# design.net
KiCad netlist of a schematic drawn in Altium Designer
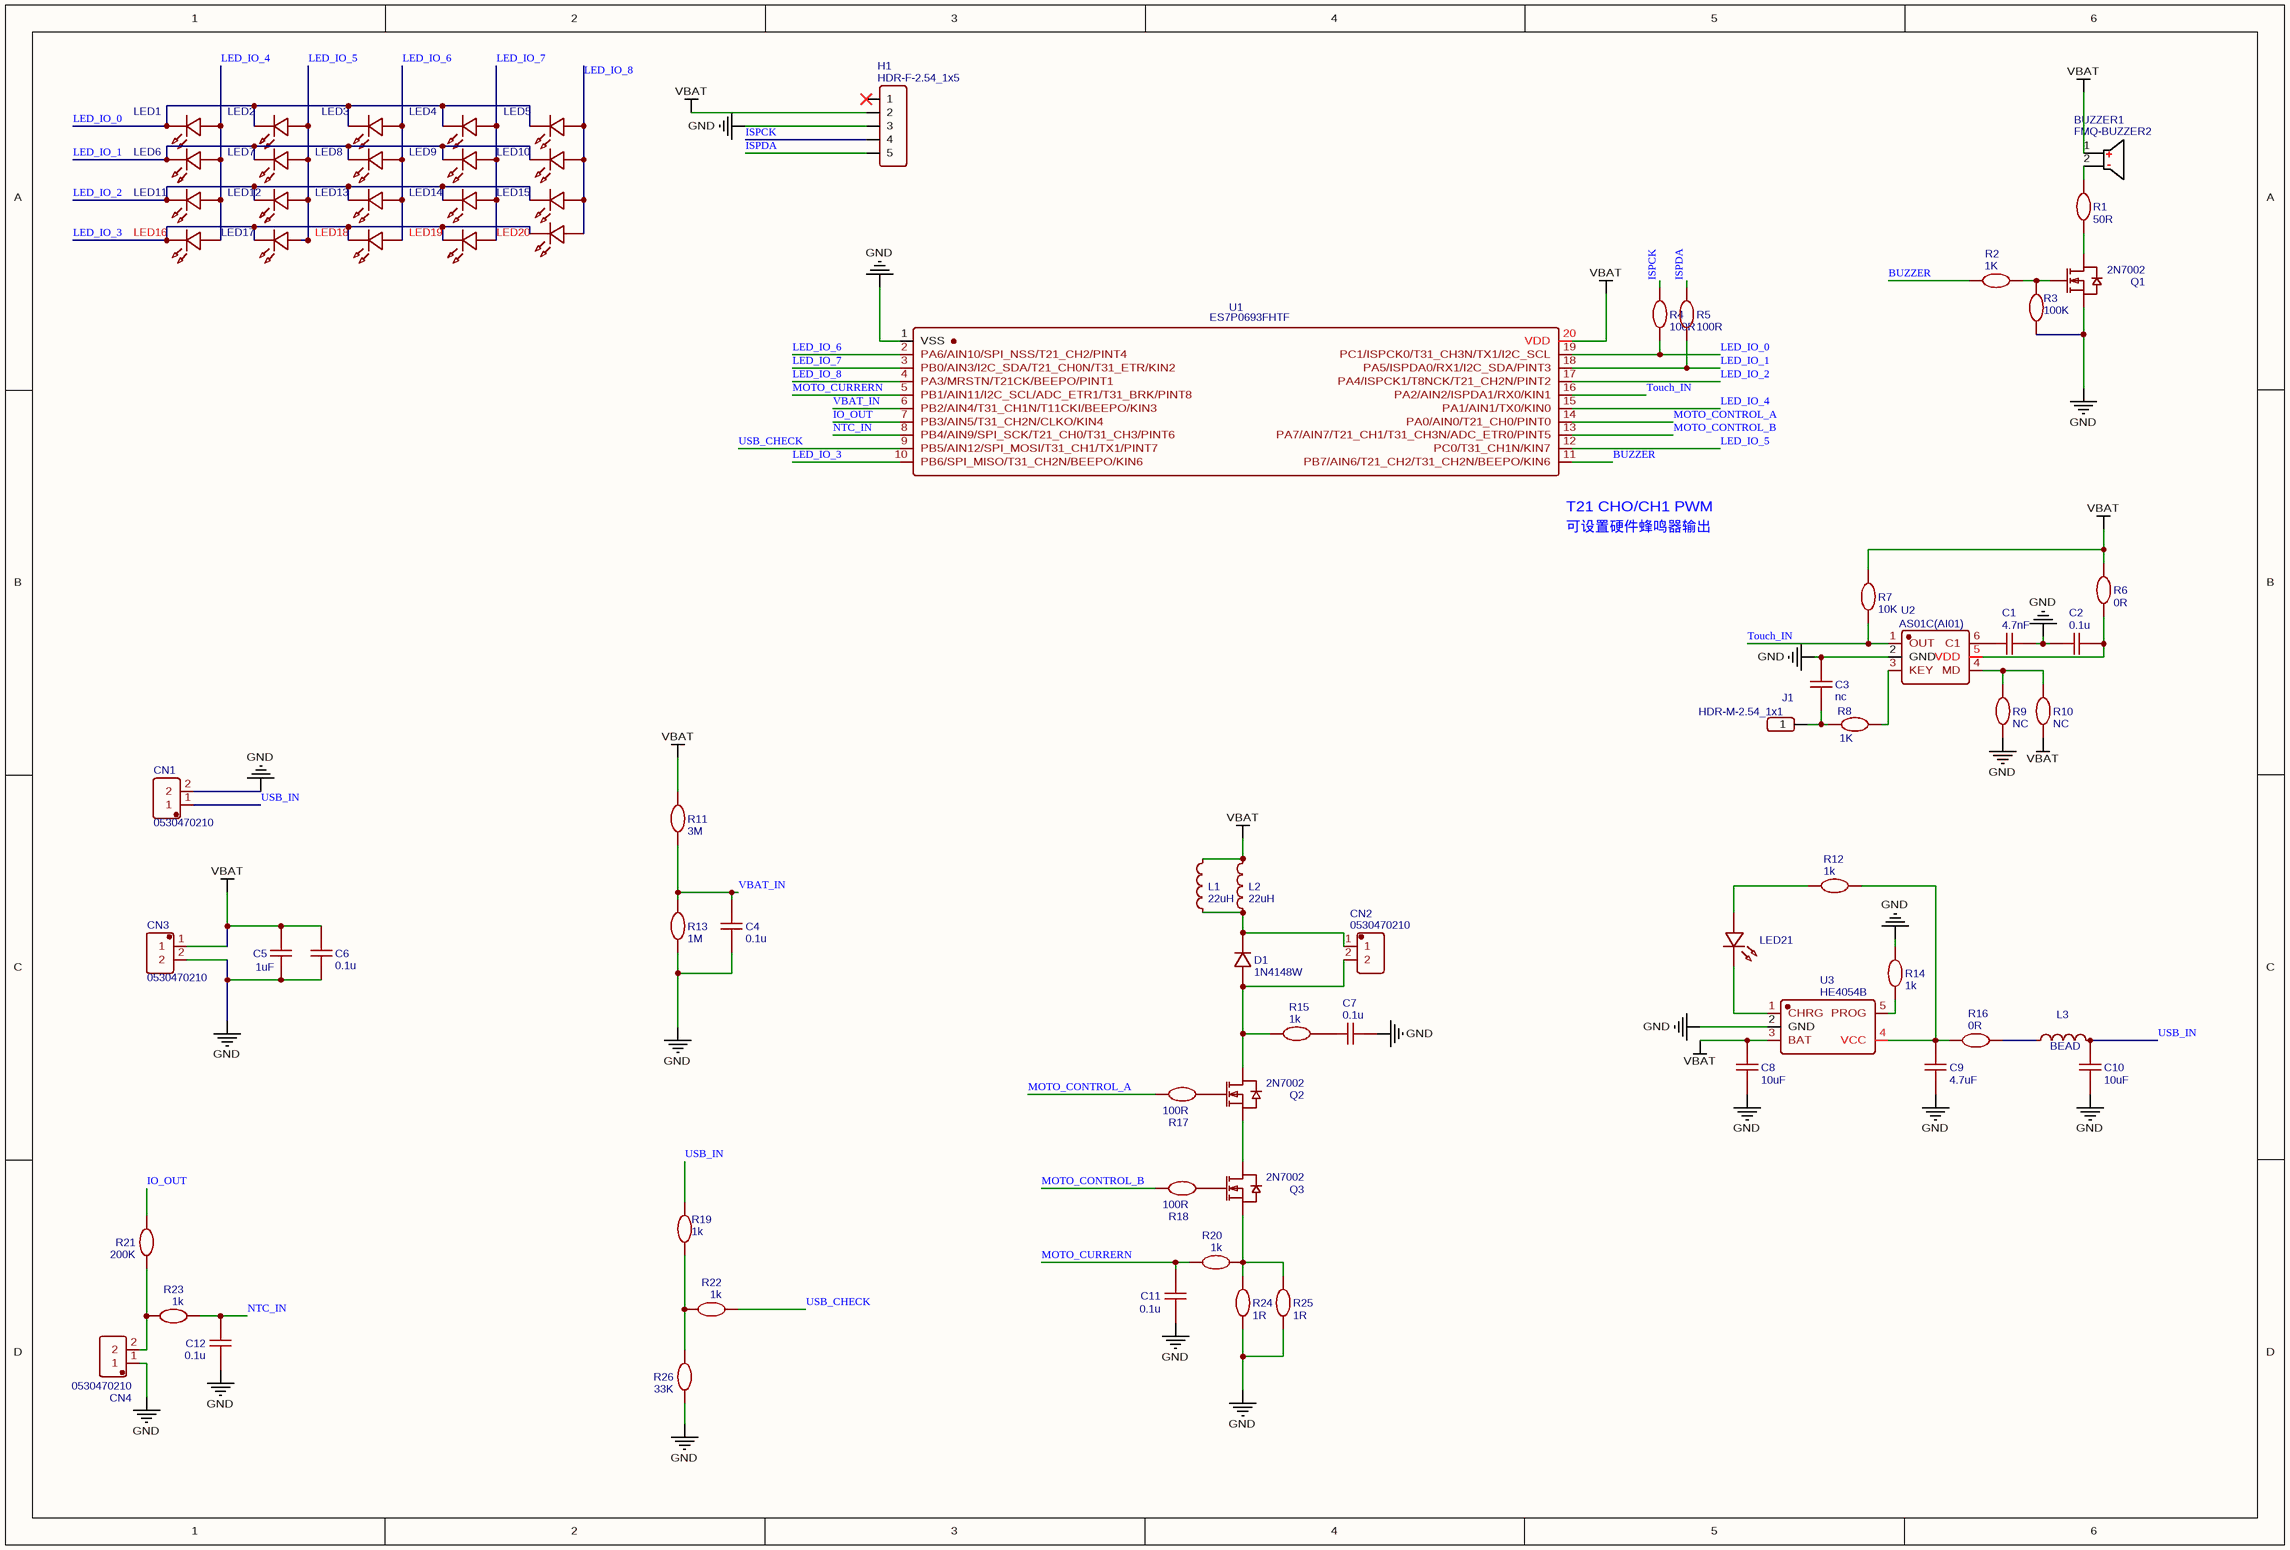
[diagram p0: 搅拌杯原理图.schdoc]

(export (version "E")
  (design (tool "Eeschema 10.0.6"))
  (components
    (comp (ref "BUZZER1")
      (value "FMQ-BUZZER2")
      (footprint "BUZ-TH_BD12.0-P7.60-D0.6-FD")
      (fields (field (name "BOM_SUPPLIER PART") "C9900006103") (field (name "CONTRIBUTOR") "LCSC"))
      (libsource (lib "altium-import") (part "root_0_FMQ-BUZZER2_"))
    )
    (comp (ref "C1")
      (value "4.7nF")
      (footprint "C0603")
      (fields (field (name "CONTRIBUTOR") "LCEDA_Lib"))
      (libsource (lib "altium-import") (part "root_0_4.7nF_"))
    )
    (comp (ref "C2")
      (value "0.1u")
      (footprint "C0603")
      (fields (field (name "CONTRIBUTOR") "LCEDA_Lib"))
      (libsource (lib "altium-import") (part "root_0_0.1u_"))
    )
    (comp (ref "C3")
      (value "nc")
      (footprint "C0603")
      (fields (field (name "CONTRIBUTOR") "LCEDA_Lib"))
      (libsource (lib "altium-import") (part "root_1_nc_"))
    )
    (comp (ref "C4")
      (value "0.1u")
      (footprint "C0603")
      (fields (field (name "CONTRIBUTOR") "LCEDA_Lib"))
      (libsource (lib "") (part "root_1_0.1u__1"))
    )
    (comp (ref "C5")
      (value "1uF")
      (footprint "C0603")
      (fields (field (name "CONTRIBUTOR") "LCEDA_Lib"))
      (libsource (lib "altium-import") (part "root_3_1uF_"))
    )
    (comp (ref "C6")
      (value "0.1u")
      (footprint "C0603")
      (fields (field (name "CONTRIBUTOR") "LCEDA_Lib"))
      (libsource (lib "altium-import") (part "root_3_0.1u_"))
    )
    (comp (ref "C7")
      (value "0.1u")
      (footprint "C0603")
      (fields (field (name "CONTRIBUTOR") "LCEDA_Lib"))
      (libsource (lib "altium-import") (part "root_2_0.1u_"))
    )
    (comp (ref "C8")
      (value "10uF")
      (footprint "C0603")
      (fields (field (name "CONTRIBUTOR") "LCEDA_Lib"))
      (libsource (lib "altium-import") (part "root_1_10uF_"))
    )
    (comp (ref "C9")
      (value "4.7uF")
      (footprint "C0603")
      (fields (field (name "CONTRIBUTOR") "LCEDA_Lib"))
      (libsource (lib "altium-import") (part "root_1_4.7uF_"))
    )
    (comp (ref "C10")
      (value "10uF")
      (footprint "C0603")
      (fields (field (name "CONTRIBUTOR") "LCEDA_Lib"))
      (libsource (lib "altium-import") (part "root_1_10uF_"))
    )
    (comp (ref "C11")
      (value "0.1u")
      (footprint "C0603")
      (fields (field (name "CONTRIBUTOR") "LCEDA_Lib"))
      (libsource (lib "altium-import") (part "root_1_0.1u_"))
    )
    (comp (ref "C12")
      (value "0.1u")
      (footprint "C0603")
      (fields (field (name "CONTRIBUTOR") "LCEDA_Lib"))
      (libsource (lib "") (part "root_3_0.1u__1"))
    )
    (comp (ref "CN1")
      (value "0530470210")
      (footprint "CONN-TH_0530470210")
      (fields (field (name "BOM_SUPPLIER PART") "C114130") (field (name "CONTRIBUTOR") "LCSC"))
      (libsource (lib "altium-import") (part "root_0_mirrored_0530470210_"))
    )
    (comp (ref "CN2")
      (value "0530470210")
      (footprint "CONN-TH_0530470210")
      (fields (field (name "BOM_SUPPLIER PART") "C114130") (field (name "CONTRIBUTOR") "LCSC"))
      (libsource (lib "altium-import") (part "root_0_0530470210_"))
    )
    (comp (ref "CN3")
      (value "0530470210")
      (footprint "CONN-TH_0530470210")
      (fields (field (name "BOM_SUPPLIER PART") "C114130") (field (name "CONTRIBUTOR") "LCSC"))
      (libsource (lib "") (part "root_0_mirrored_0530470210__1"))
    )
    (comp (ref "CN4")
      (value "0530470210")
      (footprint "CONN-TH_0530470210")
      (fields (field (name "BOM_SUPPLIER PART") "C114130") (field (name "CONTRIBUTOR") "LCSC"))
      (libsource (lib "") (part "root_0_0530470210__1"))
    )
    (comp (ref "D1")
      (value "1N4148W")
      (footprint "SOD-123FL_L2.6-W1.6-LS3.4-RD")
      (fields (field (name "BOM_SUPPLIER PART") "C129216") (field (name "CONTRIBUTOR") "LCEDA_Lib"))
      (libsource (lib "altium-import") (part "root_1_1N4148W_"))
    )
    (comp (ref "H1")
      (value "HDR-F-2.54_1x5")
      (footprint "1.27mm_5PIN")
      (fields (field (name "BOM_SUPPLIER PART") "C50950") (field (name "CONTRIBUTOR") "LCEDA_Lib"))
      (libsource (lib "altium-import") (part "root_0_HDR-F-2.54_1x5_"))
    )
    (comp (ref "J1")
      (value "HDR-M-2.54_1x1")
      (footprint "HDR-M-2.54_1X1")
      (fields (field (name "BOM_SUPPLIER PART") "C81276") (field (name "CONTRIBUTOR") "LCEDA_Lib"))
      (libsource (lib "altium-import") (part "root_2_HDR-M-2.54_1x1_"))
    )
    (comp (ref "L1")
      (value "22uH")
      (footprint "L0603")
      (fields (field (name "CONTRIBUTOR") "LCEDA_Lib"))
      (libsource (lib "altium-import") (part "root_1_22uH_"))
    )
    (comp (ref "L2")
      (value "22uH")
      (footprint "L0603")
      (fields (field (name "CONTRIBUTOR") "LCEDA_Lib"))
      (libsource (lib "altium-import") (part "root_1_22uH_"))
    )
    (comp (ref "L3")
      (value "BEAD")
      (footprint "L0603")
      (fields (field (name "CONTRIBUTOR") "LCEDA_Lib"))
      (libsource (lib "altium-import") (part "root_0_22uH_"))
    )
    (comp (ref "LED1")
      (value "LED-0603_W")
      (footprint "LED0603-FD_WHITE")
      (fields
        (field (name "BOM_MANUFACTURER PART") "17-21SURC/S530-A3/TR8")
        (field (name "BOM_SUPPLIER PART") "C72037")
        (field (name "CONTRIBUTOR") "LCEDA_Lib")
      )
      (libsource (lib "altium-import") (part "root_2_LED-0603_W_"))
    )
    (comp (ref "LED2")
      (value "LED-0603_W")
      (footprint "LED0603-FD_WHITE")
      (fields
        (field (name "BOM_MANUFACTURER PART") "17-21SURC/S530-A3/TR8")
        (field (name "BOM_SUPPLIER PART") "C72037")
        (field (name "CONTRIBUTOR") "LCEDA_Lib")
      )
      (libsource (lib "altium-import") (part "root_2_LED-0603_W_"))
    )
    (comp (ref "LED3")
      (value "LED-0603_W")
      (footprint "LED0603-FD_WHITE")
      (fields
        (field (name "BOM_MANUFACTURER PART") "17-21SURC/S530-A3/TR8")
        (field (name "BOM_SUPPLIER PART") "C72037")
        (field (name "CONTRIBUTOR") "LCEDA_Lib")
      )
      (libsource (lib "altium-import") (part "root_2_LED-0603_W_"))
    )
    (comp (ref "LED4")
      (value "LED-0603_W")
      (footprint "LED0603-FD_WHITE")
      (fields
        (field (name "BOM_MANUFACTURER PART") "17-21SURC/S530-A3/TR8")
        (field (name "BOM_SUPPLIER PART") "C72037")
        (field (name "CONTRIBUTOR") "LCEDA_Lib")
      )
      (libsource (lib "altium-import") (part "root_2_LED-0603_W_"))
    )
    (comp (ref "LED5")
      (value "LED-0603_W")
      (footprint "LED0603-FD_WHITE")
      (fields
        (field (name "BOM_MANUFACTURER PART") "17-21SURC/S530-A3/TR8")
        (field (name "BOM_SUPPLIER PART") "C72037")
        (field (name "CONTRIBUTOR") "LCEDA_Lib")
      )
      (libsource (lib "altium-import") (part "root_2_LED-0603_W_"))
    )
    (comp (ref "LED6")
      (value "LED-0603_W")
      (footprint "LED0603-FD_WHITE")
      (fields
        (field (name "BOM_MANUFACTURER PART") "17-21SURC/S530-A3/TR8")
        (field (name "BOM_SUPPLIER PART") "C72037")
        (field (name "CONTRIBUTOR") "LCEDA_Lib")
      )
      (libsource (lib "altium-import") (part "root_2_LED-0603_W_"))
    )
    (comp (ref "LED7")
      (value "LED-0603_W")
      (footprint "LED0603-FD_WHITE")
      (fields
        (field (name "BOM_MANUFACTURER PART") "17-21SURC/S530-A3/TR8")
        (field (name "BOM_SUPPLIER PART") "C72037")
        (field (name "CONTRIBUTOR") "LCEDA_Lib")
      )
      (libsource (lib "altium-import") (part "root_2_LED-0603_W_"))
    )
    (comp (ref "LED8")
      (value "LED-0603_W")
      (footprint "LED0603-FD_WHITE")
      (fields
        (field (name "BOM_MANUFACTURER PART") "17-21SURC/S530-A3/TR8")
        (field (name "BOM_SUPPLIER PART") "C72037")
        (field (name "CONTRIBUTOR") "LCEDA_Lib")
      )
      (libsource (lib "altium-import") (part "root_2_LED-0603_W_"))
    )
    (comp (ref "LED9")
      (value "LED-0603_W")
      (footprint "LED0603-FD_WHITE")
      (fields
        (field (name "BOM_MANUFACTURER PART") "17-21SURC/S530-A3/TR8")
        (field (name "BOM_SUPPLIER PART") "C72037")
        (field (name "CONTRIBUTOR") "LCEDA_Lib")
      )
      (libsource (lib "altium-import") (part "root_2_LED-0603_W_"))
    )
    (comp (ref "LED10")
      (value "LED-0603_W")
      (footprint "LED0603-FD_WHITE")
      (fields
        (field (name "BOM_MANUFACTURER PART") "17-21SURC/S530-A3/TR8")
        (field (name "BOM_SUPPLIER PART") "C72037")
        (field (name "CONTRIBUTOR") "LCEDA_Lib")
      )
      (libsource (lib "altium-import") (part "root_2_LED-0603_W_"))
    )
    (comp (ref "LED11")
      (value "LED-0603_W")
      (footprint "LED0603-FD_WHITE")
      (fields
        (field (name "BOM_MANUFACTURER PART") "17-21SURC/S530-A3/TR8")
        (field (name "BOM_SUPPLIER PART") "C72037")
        (field (name "CONTRIBUTOR") "LCEDA_Lib")
      )
      (libsource (lib "altium-import") (part "root_2_LED-0603_W_"))
    )
    (comp (ref "LED12")
      (value "LED-0603_W")
      (footprint "LED0603-FD_WHITE")
      (fields
        (field (name "BOM_MANUFACTURER PART") "17-21SURC/S530-A3/TR8")
        (field (name "BOM_SUPPLIER PART") "C72037")
        (field (name "CONTRIBUTOR") "LCEDA_Lib")
      )
      (libsource (lib "altium-import") (part "root_2_LED-0603_W_"))
    )
    (comp (ref "LED13")
      (value "LED-0603_W")
      (footprint "LED0603-FD_WHITE")
      (fields
        (field (name "BOM_MANUFACTURER PART") "17-21SURC/S530-A3/TR8")
        (field (name "BOM_SUPPLIER PART") "C72037")
        (field (name "CONTRIBUTOR") "LCEDA_Lib")
      )
      (libsource (lib "altium-import") (part "root_2_LED-0603_W_"))
    )
    (comp (ref "LED14")
      (value "LED-0603_W")
      (footprint "LED0603-FD_WHITE")
      (fields
        (field (name "BOM_MANUFACTURER PART") "17-21SURC/S530-A3/TR8")
        (field (name "BOM_SUPPLIER PART") "C72037")
        (field (name "CONTRIBUTOR") "LCEDA_Lib")
      )
      (libsource (lib "altium-import") (part "root_2_LED-0603_W_"))
    )
    (comp (ref "LED15")
      (value "LED-0603_W")
      (footprint "LED0603-FD_WHITE")
      (fields
        (field (name "BOM_MANUFACTURER PART") "17-21SURC/S530-A3/TR8")
        (field (name "BOM_SUPPLIER PART") "C72037")
        (field (name "CONTRIBUTOR") "LCEDA_Lib")
      )
      (libsource (lib "altium-import") (part "root_2_LED-0603_W_"))
    )
    (comp (ref "LED16")
      (value "LED-0603_W")
      (footprint "LED0603-FD_WHITE")
      (fields
        (field (name "BOM_MANUFACTURER PART") "17-21SURC/S530-A3/TR8")
        (field (name "BOM_SUPPLIER PART") "C72037")
        (field (name "CONTRIBUTOR") "LCEDA_Lib")
      )
      (libsource (lib "altium-import") (part "root_2_LED-0603_W_"))
    )
    (comp (ref "LED17")
      (value "LED-0603_W")
      (footprint "LED0603-FD_WHITE")
      (fields
        (field (name "BOM_MANUFACTURER PART") "17-21SURC/S530-A3/TR8")
        (field (name "BOM_SUPPLIER PART") "C72037")
        (field (name "CONTRIBUTOR") "LCEDA_Lib")
      )
      (libsource (lib "altium-import") (part "root_2_LED-0603_W_"))
    )
    (comp (ref "LED18")
      (value "LED-0603_W")
      (footprint "LED0603-FD_WHITE")
      (fields
        (field (name "BOM_MANUFACTURER PART") "17-21SURC/S530-A3/TR8")
        (field (name "BOM_SUPPLIER PART") "C72037")
        (field (name "CONTRIBUTOR") "LCEDA_Lib")
      )
      (libsource (lib "altium-import") (part "root_2_LED-0603_W_"))
    )
    (comp (ref "LED19")
      (value "LED-0603_W")
      (footprint "LED0603-FD_WHITE")
      (fields
        (field (name "BOM_MANUFACTURER PART") "17-21SURC/S530-A3/TR8")
        (field (name "BOM_SUPPLIER PART") "C72037")
        (field (name "CONTRIBUTOR") "LCEDA_Lib")
      )
      (libsource (lib "altium-import") (part "root_2_LED-0603_W_"))
    )
    (comp (ref "LED20")
      (value "LED-0603_W")
      (footprint "LED0603-FD_WHITE")
      (fields
        (field (name "BOM_MANUFACTURER PART") "17-21SURC/S530-A3/TR8")
        (field (name "BOM_SUPPLIER PART") "C72037")
        (field (name "CONTRIBUTOR") "LCEDA_Lib")
      )
      (libsource (lib "altium-import") (part "root_2_LED-0603_W_"))
    )
    (comp (ref "LED21")
      (value "LED-0603_W")
      (footprint "LED0603-FD_WHITE")
      (fields
        (field (name "BOM_MANUFACTURER PART") "17-21SURC/S530-A3/TR8")
        (field (name "BOM_SUPPLIER PART") "C72037")
        (field (name "CONTRIBUTOR") "LCEDA_Lib")
      )
      (libsource (lib "altium-import") (part "root_3_LED-0603_W_"))
    )
    (comp (ref "Q1")
      (value "2N7002")
      (footprint "SOT-23_L2.9-W1.3-P0.95-LS2.4-BR")
      (fields
        (field (name "BOM_MANUFACTURER PART") "2N7002,215")
        (field (name "BOM_SUPPLIER PART") "C65189")
        (field (name "CONTRIBUTOR") "LCEDA_Lib")
      )
      (libsource (lib "altium-import") (part "root_2_2N7002_"))
    )
    (comp (ref "Q2")
      (value "2N7002")
      (footprint "SOT-23_L2.9-W1.3-P0.95-LS2.4-BR")
      (fields
        (field (name "BOM_MANUFACTURER PART") "2N7002,215")
        (field (name "BOM_SUPPLIER PART") "C65189")
        (field (name "CONTRIBUTOR") "LCEDA_Lib")
      )
      (libsource (lib "altium-import") (part "root_2_2N7002_"))
    )
    (comp (ref "Q3")
      (value "2N7002")
      (footprint "SOT-23_L2.9-W1.3-P0.95-LS2.4-BR")
      (fields
        (field (name "BOM_MANUFACTURER PART") "2N7002,215")
        (field (name "BOM_SUPPLIER PART") "C65189")
        (field (name "CONTRIBUTOR") "LCEDA_Lib")
      )
      (libsource (lib "altium-import") (part "root_2_2N7002_"))
    )
    (comp (ref "R1")
      (value "50R")
      (footprint "R0603")
      (fields (field (name "CONTRIBUTOR") "LCEDA_Lib"))
      (libsource (lib "altium-import") (part "root_3_100R_"))
    )
    (comp (ref "R2")
      (value "1K")
      (footprint "R0603")
      (fields (field (name "CONTRIBUTOR") "LCEDA_Lib"))
      (libsource (lib "altium-import") (part "root_2_1K_"))
    )
    (comp (ref "R3")
      (value "100K")
      (footprint "R0603")
      (fields (field (name "CONTRIBUTOR") "LCEDA_Lib"))
      (libsource (lib "altium-import") (part "root_3_1K_"))
    )
    (comp (ref "R4")
      (value "100R")
      (footprint "R0603")
      (fields (field (name "CONTRIBUTOR") "LCEDA_Lib"))
      (libsource (lib "altium-import") (part "root_3_100R_"))
    )
    (comp (ref "R5")
      (value "100R")
      (footprint "R0603")
      (fields (field (name "CONTRIBUTOR") "LCEDA_Lib"))
      (libsource (lib "altium-import") (part "root_3_100R_"))
    )
    (comp (ref "R6")
      (value "0R")
      (footprint "R0603")
      (fields (field (name "CONTRIBUTOR") "LCEDA_Lib"))
      (libsource (lib "altium-import") (part "root_1_NC_"))
    )
    (comp (ref "R7")
      (value "10K")
      (footprint "R0603")
      (fields (field (name "CONTRIBUTOR") "LCEDA_Lib"))
      (libsource (lib "altium-import") (part "root_1_NC_"))
    )
    (comp (ref "R8")
      (value "1K")
      (footprint "R0603")
      (fields (field (name "CONTRIBUTOR") "LCEDA_Lib"))
      (libsource (lib "altium-import") (part "root_2_1K_"))
    )
    (comp (ref "R9")
      (value "NC")
      (footprint "R0603")
      (fields (field (name "CONTRIBUTOR") "LCEDA_Lib"))
      (libsource (lib "altium-import") (part "root_1_NC_"))
    )
    (comp (ref "R10")
      (value "NC")
      (footprint "R0603")
      (fields (field (name "CONTRIBUTOR") "LCEDA_Lib"))
      (libsource (lib "altium-import") (part "root_1_NC_"))
    )
    (comp (ref "R11")
      (value "3M")
      (footprint "R0603")
      (fields (field (name "CONTRIBUTOR") "LCEDA_Lib"))
      (libsource (lib "altium-import") (part "root_1_430k_"))
    )
    (comp (ref "R12")
      (value "1k")
      (footprint "R0603")
      (fields (field (name "CONTRIBUTOR") "LCEDA_Lib"))
      (libsource (lib "") (part "root_2_1k__1"))
    )
    (comp (ref "R13")
      (value "1M")
      (footprint "R0603")
      (fields (field (name "CONTRIBUTOR") "LCEDA_Lib"))
      (libsource (lib "altium-import") (part "root_1_430K_"))
    )
    (comp (ref "R14")
      (value "1k")
      (footprint "R0603")
      (fields (field (name "CONTRIBUTOR") "LCEDA_Lib"))
      (libsource (lib "altium-import") (part "root_1_1k_"))
    )
    (comp (ref "R15")
      (value "1k")
      (footprint "R0603")
      (fields (field (name "CONTRIBUTOR") "LCEDA_Lib"))
      (libsource (lib "") (part "root_2_1k__1"))
    )
    (comp (ref "R16")
      (value "0R")
      (footprint "R0603")
      (fields (field (name "CONTRIBUTOR") "LCEDA_Lib"))
      (libsource (lib "altium-import") (part "root_0_NC_"))
    )
    (comp (ref "R17")
      (value "100R")
      (footprint "R0603")
      (fields (field (name "CONTRIBUTOR") "LCEDA_Lib"))
      (libsource (lib "altium-import") (part "root_2_100R_"))
    )
    (comp (ref "R18")
      (value "100R")
      (footprint "R0603")
      (fields (field (name "CONTRIBUTOR") "LCEDA_Lib"))
      (libsource (lib "altium-import") (part "root_2_100R_"))
    )
    (comp (ref "R19")
      (value "1k")
      (footprint "R0603")
      (fields (field (name "CONTRIBUTOR") "LCEDA_Lib"))
      (libsource (lib "altium-import") (part "root_3_1k_"))
    )
    (comp (ref "R20")
      (value "1k")
      (footprint "R0603")
      (fields (field (name "CONTRIBUTOR") "LCEDA_Lib"))
      (libsource (lib "altium-import") (part "root_0_1k_"))
    )
    (comp (ref "R21")
      (value "200K")
      (footprint "R0603")
      (fields (field (name "CONTRIBUTOR") "LCEDA_Lib"))
      (libsource (lib "altium-import") (part "root_3_33K_"))
    )
    (comp (ref "R22")
      (value "1k")
      (footprint "R0603")
      (fields (field (name "CONTRIBUTOR") "LCEDA_Lib"))
      (libsource (lib "altium-import") (part "root_2_1k_"))
    )
    (comp (ref "R23")
      (value "1k")
      (footprint "R0603")
      (fields (field (name "CONTRIBUTOR") "LCEDA_Lib"))
      (libsource (lib "altium-import") (part "root_2_1k_"))
    )
    (comp (ref "R24")
      (value "1R")
      (footprint "R1206")
      (fields (field (name "CONTRIBUTOR") "LCEDA_Lib"))
      (libsource (lib "altium-import") (part "root_1_1R_"))
    )
    (comp (ref "R25")
      (value "1R")
      (footprint "R1206")
      (fields (field (name "CONTRIBUTOR") "LCEDA_Lib"))
      (libsource (lib "altium-import") (part "root_1_1R_"))
    )
    (comp (ref "R26")
      (value "33K")
      (footprint "R0603")
      (fields (field (name "CONTRIBUTOR") "LCEDA_Lib"))
      (libsource (lib "altium-import") (part "root_3_33K_"))
    )
    (comp (ref "U1")
      (value "ES7P0693FHTF")
      (footprint "TSOP20")
      (fields (field (name "CONTRIBUTOR") "zime_zl"))
      (libsource (lib "altium-import") (part "root_0_ES7P0693FHTF_"))
    )
    (comp (ref "U2")
      (value "AS01C(AI01)")
      (footprint "SOT-23-6_L2.9-W1.6-P0.95-LS2.8-BL")
      (fields (field (name "BOM_SUPPLIER PART") "C389617") (field (name "CONTRIBUTOR") "LCSC"))
      (libsource (lib "altium-import") (part "root_0_AS01C(AI01)_"))
    )
    (comp (ref "U3")
      (value "HE4054B")
      (footprint "SOT-23-5_L3.0-W1.7-P0.95-LS2.8-BR")
      (fields (field (name "BOM_SUPPLIER PART") "C711953") (field (name "CONTRIBUTOR") "LCSC"))
      (libsource (lib "altium-import") (part "root_0_HE4054B_"))
    )
  )
  (nets
    (net (code "1") (name "/BUZZER") (class "Default")
      (node (ref "R2") (pin "2") (pinfunction "2_2") (pintype "passive"))
      (node (ref "U1") (pin "11") (pinfunction "PB7/AIN6/T21_CH2/T31_CH2N/BEEPO/KIN6_11") (pintype "passive"))
    )
    (net (code "2") (name "/IO_OUT") (class "Default")
      (node (ref "R21") (pin "1") (pinfunction "1_1") (pintype "passive"))
      (node (ref "U1") (pin "7") (pinfunction "PB3/AIN5/T31_CH2N/CLKO/KIN4_7") (pintype "passive"))
    )
    (net (code "3") (name "/ISPCK") (class "Default")
      (node (ref "H1") (pin "4") (pinfunction "4_4") (pintype "passive"))
      (node (ref "R4") (pin "1") (pinfunction "1_1") (pintype "passive"))
    )
    (net (code "4") (name "/ISPDA") (class "Default")
      (node (ref "H1") (pin "5") (pinfunction "5_5") (pintype "passive"))
      (node (ref "R5") (pin "1") (pinfunction "1_1") (pintype "passive"))
    )
    (net (code "5") (name "/LED_IO_0") (class "Default")
      (node (ref "LED1") (pin "2") (pinfunction "2_2") (pintype "passive"))
      (node (ref "LED2") (pin "2") (pinfunction "2_2") (pintype "passive"))
      (node (ref "LED3") (pin "2") (pinfunction "2_2") (pintype "passive"))
      (node (ref "LED4") (pin "2") (pinfunction "2_2") (pintype "passive"))
      (node (ref "LED5") (pin "2") (pinfunction "2_2") (pintype "passive"))
      (node (ref "R4") (pin "2") (pinfunction "2_2") (pintype "passive"))
      (node (ref "U1") (pin "19") (pinfunction "PC1/ISPCK0/T31_CH3N/TX1/I2C_SCL_19") (pintype "passive"))
    )
    (net (code "6") (name "/LED_IO_1") (class "Default")
      (node (ref "LED10") (pin "2") (pinfunction "2_2") (pintype "passive"))
      (node (ref "LED6") (pin "2") (pinfunction "2_2") (pintype "passive"))
      (node (ref "LED7") (pin "2") (pinfunction "2_2") (pintype "passive"))
      (node (ref "LED8") (pin "2") (pinfunction "2_2") (pintype "passive"))
      (node (ref "LED9") (pin "2") (pinfunction "2_2") (pintype "passive"))
      (node (ref "R5") (pin "2") (pinfunction "2_2") (pintype "passive"))
      (node (ref "U1") (pin "18") (pinfunction "PA5/ISPDA0/RX1/I2C_SDA/PINT3_18") (pintype "passive"))
    )
    (net (code "7") (name "/LED_IO_2") (class "Default")
      (node (ref "LED11") (pin "2") (pinfunction "2_2") (pintype "passive"))
      (node (ref "LED12") (pin "2") (pinfunction "2_2") (pintype "passive"))
      (node (ref "LED13") (pin "2") (pinfunction "2_2") (pintype "passive"))
      (node (ref "LED14") (pin "2") (pinfunction "2_2") (pintype "passive"))
      (node (ref "LED15") (pin "2") (pinfunction "2_2") (pintype "passive"))
      (node (ref "U1") (pin "17") (pinfunction "PA4/ISPCK1/T8NCK/T21_CH2N/PINT2_17") (pintype "passive"))
    )
    (net (code "8") (name "/LED_IO_3") (class "Default")
      (node (ref "LED16") (pin "2") (pinfunction "2_2") (pintype "passive"))
      (node (ref "LED17") (pin "2") (pinfunction "2_2") (pintype "passive"))
      (node (ref "LED18") (pin "2") (pinfunction "2_2") (pintype "passive"))
      (node (ref "LED19") (pin "2") (pinfunction "2_2") (pintype "passive"))
      (node (ref "LED20") (pin "2") (pinfunction "2_2") (pintype "passive"))
      (node (ref "U1") (pin "10") (pinfunction "PB6/SPI_MISO/T31_CH2N/BEEPO/KIN6_10") (pintype "passive"))
    )
    (net (code "9") (name "/LED_IO_4") (class "Default")
      (node (ref "LED1") (pin "1") (pinfunction "1_1") (pintype "passive"))
      (node (ref "LED11") (pin "1") (pinfunction "1_1") (pintype "passive"))
      (node (ref "LED16") (pin "1") (pinfunction "1_1") (pintype "passive"))
      (node (ref "LED6") (pin "1") (pinfunction "1_1") (pintype "passive"))
      (node (ref "U1") (pin "15") (pinfunction "PA1/AIN1/TX0/KIN0_15") (pintype "passive"))
    )
    (net (code "10") (name "/LED_IO_5") (class "Default")
      (node (ref "LED12") (pin "1") (pinfunction "1_1") (pintype "passive"))
      (node (ref "LED17") (pin "1") (pinfunction "1_1") (pintype "passive"))
      (node (ref "LED2") (pin "1") (pinfunction "1_1") (pintype "passive"))
      (node (ref "LED7") (pin "1") (pinfunction "1_1") (pintype "passive"))
      (node (ref "U1") (pin "12") (pinfunction "PC0/T31_CH1N/KIN7_12") (pintype "passive"))
    )
    (net (code "11") (name "/LED_IO_6") (class "Default")
      (node (ref "LED13") (pin "1") (pinfunction "1_1") (pintype "passive"))
      (node (ref "LED18") (pin "1") (pinfunction "1_1") (pintype "passive"))
      (node (ref "LED3") (pin "1") (pinfunction "1_1") (pintype "passive"))
      (node (ref "LED8") (pin "1") (pinfunction "1_1") (pintype "passive"))
      (node (ref "U1") (pin "2") (pinfunction "PA6/AIN10/SPI_NSS/T21_CH2/PINT4_2") (pintype "passive"))
    )
    (net (code "12") (name "/LED_IO_7") (class "Default")
      (node (ref "LED14") (pin "1") (pinfunction "1_1") (pintype "passive"))
      (node (ref "LED19") (pin "1") (pinfunction "1_1") (pintype "passive"))
      (node (ref "LED4") (pin "1") (pinfunction "1_1") (pintype "passive"))
      (node (ref "LED9") (pin "1") (pinfunction "1_1") (pintype "passive"))
      (node (ref "U1") (pin "3") (pinfunction "PB0/AIN3/I2C_SDA/T21_CH0N/T31_ETR/KIN2_3") (pintype "passive"))
    )
    (net (code "13") (name "/LED_IO_8") (class "Default")
      (node (ref "LED10") (pin "1") (pinfunction "1_1") (pintype "passive"))
      (node (ref "LED15") (pin "1") (pinfunction "1_1") (pintype "passive"))
      (node (ref "LED20") (pin "1") (pinfunction "1_1") (pintype "passive"))
      (node (ref "LED5") (pin "1") (pinfunction "1_1") (pintype "passive"))
      (node (ref "U1") (pin "4") (pinfunction "PA3/MRSTN/T21CK/BEEPO/PINT1_4") (pintype "passive"))
    )
    (net (code "14") (name "/MOTO_CONTROL_A") (class "Default")
      (node (ref "R17") (pin "1") (pinfunction "1_1") (pintype "passive"))
      (node (ref "U1") (pin "14") (pinfunction "PA0/AIN0/T21_CH0/PINT0_14") (pintype "passive"))
    )
    (net (code "15") (name "/MOTO_CONTROL_B") (class "Default")
      (node (ref "R18") (pin "1") (pinfunction "1_1") (pintype "passive"))
      (node (ref "U1") (pin "13") (pinfunction "PA7/AIN7/T21_CH1/T31_CH3N/ADC_ETR0/PINT5_13") (pintype "passive"))
    )
    (net (code "16") (name "/MOTO_CURRERN") (class "Default")
      (node (ref "C11") (pin "2") (pinfunction "2_2") (pintype "passive"))
      (node (ref "R20") (pin "2") (pinfunction "2_2") (pintype "passive"))
      (node (ref "U1") (pin "5") (pinfunction "PB1/AIN11/I2C_SCL/ADC_ETR1/T31_BRK/PINT8_5") (pintype "passive"))
    )
    (net (code "17") (name "/NTC_IN") (class "Default")
      (node (ref "C12") (pin "1") (pinfunction "1_1") (pintype "passive"))
      (node (ref "R23") (pin "2") (pinfunction "2_2") (pintype "passive"))
      (node (ref "U1") (pin "8") (pinfunction "PB4/AIN9/SPI_SCK/T21_CH0/T31_CH3/PINT6_8") (pintype "passive"))
    )
    (net (code "18") (name "/Touch_IN") (class "Default")
      (node (ref "R7") (pin "1") (pinfunction "1_1") (pintype "passive"))
      (node (ref "U1") (pin "16") (pinfunction "PA2/AIN2/ISPDA1/RX0/KIN1_16") (pintype "passive"))
      (node (ref "U2") (pin "1") (pinfunction "OUT_1") (pintype "passive"))
    )
    (net (code "19") (name "/USB_CHECK") (class "Default")
      (node (ref "R22") (pin "2") (pinfunction "2_2") (pintype "passive"))
      (node (ref "U1") (pin "9") (pinfunction "PB5/AIN12/SPI_MOSI/T31_CH1/TX1/PINT7_9") (pintype "passive"))
    )
    (net (code "20") (name "/USB_IN") (class "Default")
      (node (ref "C10") (pin "2") (pinfunction "2_2") (pintype "passive"))
      (node (ref "CN1") (pin "1") (pinfunction "1_1") (pintype "passive"))
      (node (ref "L3") (pin "2") (pinfunction "2_2") (pintype "passive"))
      (node (ref "R19") (pin "2") (pinfunction "2_2") (pintype "passive"))
    )
    (net (code "21") (name "/VBAT_IN") (class "Default")
      (node (ref "C4") (pin "2") (pinfunction "2_2") (pintype "passive"))
      (node (ref "R11") (pin "1") (pinfunction "1_1") (pintype "passive"))
      (node (ref "R13") (pin "2") (pinfunction "2_2") (pintype "passive"))
      (node (ref "U1") (pin "6") (pinfunction "PB2/AIN4/T31_CH1N/T11CKI/BEEPO/KIN3_6") (pintype "passive"))
    )
    (net (code "22") (name "GND") (class "Default")
      (node (ref "C1") (pin "2") (pinfunction "2_2") (pintype "passive"))
      (node (ref "C10") (pin "1") (pinfunction "1_1") (pintype "passive"))
      (node (ref "C11") (pin "1") (pinfunction "1_1") (pintype "passive"))
      (node (ref "C12") (pin "2") (pinfunction "2_2") (pintype "passive"))
      (node (ref "C2") (pin "1") (pinfunction "1_1") (pintype "passive"))
      (node (ref "C3") (pin "2") (pinfunction "2_2") (pintype "passive"))
      (node (ref "C4") (pin "1") (pinfunction "1_1") (pintype "passive"))
      (node (ref "C5") (pin "2") (pinfunction "2_2") (pintype "passive"))
      (node (ref "C6") (pin "2") (pinfunction "2_2") (pintype "passive"))
      (node (ref "C7") (pin "1") (pinfunction "1_1") (pintype "passive"))
      (node (ref "C8") (pin "1") (pinfunction "1_1") (pintype "passive"))
      (node (ref "C9") (pin "1") (pinfunction "1_1") (pintype "passive"))
      (node (ref "CN1") (pin "2") (pinfunction "2_2") (pintype "passive"))
      (node (ref "CN3") (pin "2") (pinfunction "2_2") (pintype "passive"))
      (node (ref "CN4") (pin "1") (pinfunction "1_1") (pintype "passive"))
      (node (ref "H1") (pin "3") (pinfunction "3_3") (pintype "passive"))
      (node (ref "Q1") (pin "2") (pinfunction "S_2") (pintype "passive"))
      (node (ref "R13") (pin "1") (pinfunction "1_1") (pintype "passive"))
      (node (ref "R14") (pin "2") (pinfunction "2_2") (pintype "passive"))
      (node (ref "R24") (pin "1") (pinfunction "1_1") (pintype "passive"))
      (node (ref "R25") (pin "1") (pinfunction "1_1") (pintype "passive"))
      (node (ref "R26") (pin "2") (pinfunction "2_2") (pintype "passive"))
      (node (ref "R3") (pin "2") (pinfunction "2_2") (pintype "passive"))
      (node (ref "R9") (pin "1") (pinfunction "1_1") (pintype "passive"))
      (node (ref "U1") (pin "1") (pinfunction "VSS_1") (pintype "passive"))
      (node (ref "U2") (pin "2") (pinfunction "GND_2") (pintype "passive"))
      (node (ref "U3") (pin "2") (pinfunction "GND_2") (pintype "passive"))
    )
    (net (code "23") (name "Net-(BUZZER1-Pad2)") (class "Default")
      (node (ref "BUZZER1") (pin "2") (pinfunction "2_2") (pintype "passive"))
      (node (ref "R1") (pin "1") (pinfunction "1_1") (pintype "passive"))
    )
    (net (code "24") (name "Net-(C3-Pad1)") (class "Default")
      (node (ref "C3") (pin "1") (pinfunction "1_1") (pintype "passive"))
      (node (ref "J1") (pin "1") (pinfunction "1_1") (pintype "passive"))
      (node (ref "R8") (pin "2") (pinfunction "2_2") (pintype "passive"))
    )
    (net (code "25") (name "Net-(C7-Pad2)") (class "Default")
      (node (ref "C7") (pin "2") (pinfunction "2_2") (pintype "passive"))
      (node (ref "R15") (pin "1") (pinfunction "1_1") (pintype "passive"))
    )
    (net (code "26") (name "Net-(CN2-Pad1)") (class "Default")
      (node (ref "CN2") (pin "1") (pinfunction "1_1") (pintype "passive"))
      (node (ref "D1") (pin "1") (pinfunction "1_1") (pintype "passive"))
      (node (ref "L1") (pin "1") (pinfunction "1_1") (pintype "passive"))
      (node (ref "L2") (pin "1") (pinfunction "1_1") (pintype "passive"))
    )
    (net (code "27") (name "Net-(CN4-Pad2)") (class "Default")
      (node (ref "CN4") (pin "2") (pinfunction "2_2") (pintype "passive"))
      (node (ref "R21") (pin "2") (pinfunction "2_2") (pintype "passive"))
      (node (ref "R23") (pin "1") (pinfunction "1_1") (pintype "passive"))
    )
    (net (code "28") (name "Net-(L3-Pad1)") (class "Default")
      (node (ref "L3") (pin "1") (pinfunction "1_1") (pintype "passive"))
      (node (ref "R16") (pin "2") (pinfunction "2_2") (pintype "passive"))
    )
    (net (code "29") (name "Net-(LED21-Pad1)") (class "Default")
      (node (ref "LED21") (pin "1") (pinfunction "1_1") (pintype "passive"))
      (node (ref "R12") (pin "2") (pinfunction "2_2") (pintype "passive"))
    )
    (net (code "30") (name "Net-(Q1-D)") (class "Default")
      (node (ref "Q1") (pin "3") (pinfunction "D_3") (pintype "passive"))
      (node (ref "R1") (pin "2") (pinfunction "2_2") (pintype "passive"))
    )
    (net (code "31") (name "Net-(Q1-G)") (class "Default")
      (node (ref "Q1") (pin "1") (pinfunction "G_1") (pintype "passive"))
      (node (ref "R2") (pin "1") (pinfunction "1_1") (pintype "passive"))
      (node (ref "R3") (pin "1") (pinfunction "1_1") (pintype "passive"))
    )
    (net (code "32") (name "Net-(Q2-D)") (class "Default")
      (node (ref "CN2") (pin "2") (pinfunction "2_2") (pintype "passive"))
      (node (ref "D1") (pin "2") (pinfunction "2_2") (pintype "passive"))
      (node (ref "Q2") (pin "3") (pinfunction "D_3") (pintype "passive"))
      (node (ref "R15") (pin "2") (pinfunction "2_2") (pintype "passive"))
    )
    (net (code "33") (name "Net-(Q2-G)") (class "Default")
      (node (ref "Q2") (pin "1") (pinfunction "G_1") (pintype "passive"))
      (node (ref "R17") (pin "2") (pinfunction "2_2") (pintype "passive"))
    )
    (net (code "34") (name "Net-(Q2-S)") (class "Default")
      (node (ref "Q2") (pin "2") (pinfunction "S_2") (pintype "passive"))
      (node (ref "Q3") (pin "3") (pinfunction "D_3") (pintype "passive"))
    )
    (net (code "35") (name "Net-(Q3-G)") (class "Default")
      (node (ref "Q3") (pin "1") (pinfunction "G_1") (pintype "passive"))
      (node (ref "R18") (pin "2") (pinfunction "2_2") (pintype "passive"))
    )
    (net (code "36") (name "Net-(Q3-S)") (class "Default")
      (node (ref "Q3") (pin "2") (pinfunction "S_2") (pintype "passive"))
      (node (ref "R20") (pin "1") (pinfunction "1_1") (pintype "passive"))
      (node (ref "R24") (pin "2") (pinfunction "2_2") (pintype "passive"))
      (node (ref "R25") (pin "2") (pinfunction "2_2") (pintype "passive"))
    )
    (net (code "37") (name "Net-(R19-Pad1)") (class "Default")
      (node (ref "R19") (pin "1") (pinfunction "1_1") (pintype "passive"))
      (node (ref "R22") (pin "1") (pinfunction "1_1") (pintype "passive"))
      (node (ref "R26") (pin "1") (pinfunction "1_1") (pintype "passive"))
    )
    (net (code "38") (name "Net-(U2-C1)") (class "Default")
      (node (ref "C1") (pin "1") (pinfunction "1_1") (pintype "passive"))
      (node (ref "U2") (pin "6") (pinfunction "C1_6") (pintype "passive"))
    )
    (net (code "39") (name "Net-(U2-KEY)") (class "Default")
      (node (ref "R8") (pin "1") (pinfunction "1_1") (pintype "passive"))
      (node (ref "U2") (pin "3") (pinfunction "KEY_3") (pintype "passive"))
    )
    (net (code "40") (name "Net-(U2-MD)") (class "Default")
      (node (ref "R10") (pin "2") (pinfunction "2_2") (pintype "passive"))
      (node (ref "R9") (pin "2") (pinfunction "2_2") (pintype "passive"))
      (node (ref "U2") (pin "4") (pinfunction "MD_4") (pintype "passive"))
    )
    (net (code "41") (name "Net-(U2-VDD)") (class "Default")
      (node (ref "C2") (pin "2") (pinfunction "2_2") (pintype "passive"))
      (node (ref "R6") (pin "1") (pinfunction "1_1") (pintype "passive"))
      (node (ref "U2") (pin "5") (pinfunction "VDD_5") (pintype "passive"))
    )
    (net (code "42") (name "Net-(U3-CHRG)") (class "Default")
      (node (ref "LED21") (pin "2") (pinfunction "2_2") (pintype "passive"))
      (node (ref "U3") (pin "1") (pinfunction "CHRG_1") (pintype "passive"))
    )
    (net (code "43") (name "Net-(U3-PROG)") (class "Default")
      (node (ref "R14") (pin "1") (pinfunction "1_1") (pintype "passive"))
      (node (ref "U3") (pin "5") (pinfunction "PROG_5") (pintype "passive"))
    )
    (net (code "44") (name "Net-(U3-VCC)") (class "Default")
      (node (ref "C9") (pin "2") (pinfunction "2_2") (pintype "passive"))
      (node (ref "R12") (pin "1") (pinfunction "1_1") (pintype "passive"))
      (node (ref "R16") (pin "1") (pinfunction "1_1") (pintype "passive"))
      (node (ref "U3") (pin "4") (pinfunction "VCC_4") (pintype "passive"))
    )
    (net (code "45") (name "VBAT") (class "Default")
      (node (ref "BUZZER1") (pin "1") (pinfunction "1_1") (pintype "passive"))
      (node (ref "C5") (pin "1") (pinfunction "1_1") (pintype "passive"))
      (node (ref "C6") (pin "1") (pinfunction "1_1") (pintype "passive"))
      (node (ref "C8") (pin "2") (pinfunction "2_2") (pintype "passive"))
      (node (ref "CN3") (pin "1") (pinfunction "1_1") (pintype "passive"))
      (node (ref "H1") (pin "2") (pinfunction "2_2") (pintype "passive"))
      (node (ref "L1") (pin "2") (pinfunction "2_2") (pintype "passive"))
      (node (ref "L2") (pin "2") (pinfunction "2_2") (pintype "passive"))
      (node (ref "R10") (pin "1") (pinfunction "1_1") (pintype "passive"))
      (node (ref "R11") (pin "2") (pinfunction "2_2") (pintype "passive"))
      (node (ref "R6") (pin "2") (pinfunction "2_2") (pintype "passive"))
      (node (ref "R7") (pin "2") (pinfunction "2_2") (pintype "passive"))
      (node (ref "U1") (pin "20") (pinfunction "VDD_20") (pintype "passive"))
      (node (ref "U3") (pin "3") (pinfunction "BAT_3") (pintype "passive"))
    )
    (net (code "46") (name "unconnected-(H1-Pad1)") (class "Default")
      (node (ref "H1") (pin "1") (pinfunction "1_1") (pintype "passive+no_connect"))
    )
  )
)
